# Brakeout_board_-_VEML7700.net
KiCad netlist of a schematic drawn in EAGLE
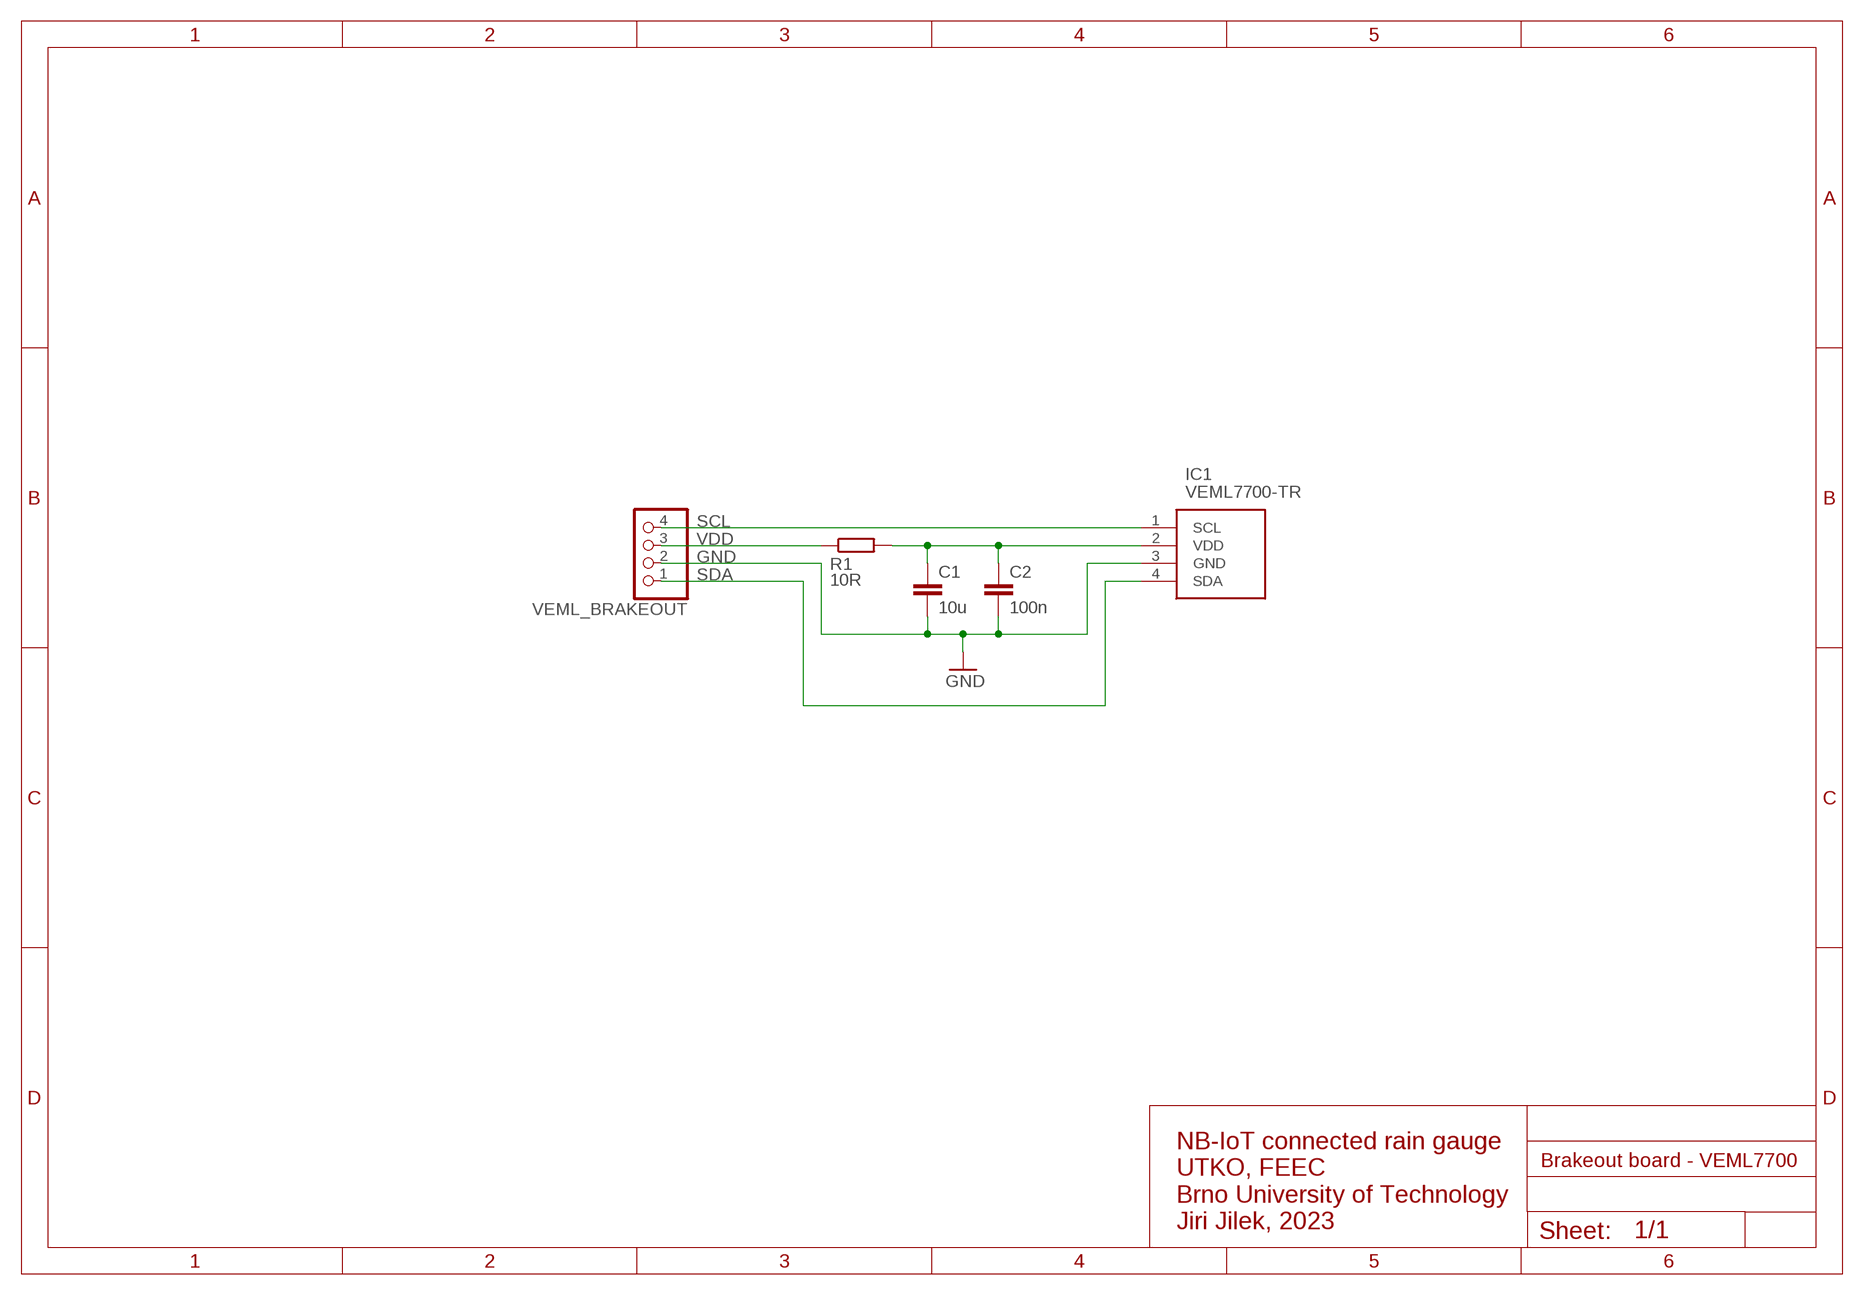
[diagram p0: schematic, sheet 1]

(export (version "E")
  (design (tool "Eeschema 10.0.6"))
  (components
    (comp (ref "C1")
      (value "10u")
      (footprint "eagle-import:C0805")
      (libsource (lib "eagle-import") (part "C-EUC0805"))
    )
    (comp (ref "C2")
      (value "100n")
      (footprint "eagle-import:C0805")
      (libsource (lib "eagle-import") (part "C-EUC0805"))
    )
    (comp (ref "IC1")
      (value "VEML7700-TR")
      (footprint "eagle-import:VEML7700")
      (fields (field (name "MOUSER_PART_NUMBER") "78-VEML7700-TR"))
      (libsource (lib "eagle-import") (part "VEML7700-TR"))
    )
    (comp (ref "R1")
      (value "10R")
      (footprint "eagle-import:R0805")
      (libsource (lib "eagle-import") (part "R-EU_R0805"))
    )
    (comp (ref "VEML_BRAKEOUT")
      (value "PINHD-1X4")
      (footprint "eagle-import:1X04")
      (libsource (lib "eagle-import") (part "PINHD-1X4"))
    )
  )
  (nets
    (net (code "1") (name "/SCL") (class "Default")
      (node (ref "IC1") (pin "1") (pinfunction "SCL_1") (pintype "bidirectional"))
      (node (ref "VEML_BRAKEOUT") (pin "4") (pinfunction "4_4") (pintype "passive"))
    )
    (net (code "2") (name "/SDA") (class "Default")
      (node (ref "IC1") (pin "4") (pinfunction "SDA_4") (pintype "bidirectional"))
      (node (ref "VEML_BRAKEOUT") (pin "1") (pinfunction "1_1") (pintype "passive"))
    )
    (net (code "3") (name "/VDD") (class "Default")
      (node (ref "R1") (pin "1") (pinfunction "1_1") (pintype "passive"))
      (node (ref "VEML_BRAKEOUT") (pin "3") (pinfunction "3_3") (pintype "passive"))
    )
    (net (code "4") (name "GND") (class "Default")
      (node (ref "C1") (pin "2") (pinfunction "2_2") (pintype "passive"))
      (node (ref "C2") (pin "2") (pinfunction "2_2") (pintype "passive"))
      (node (ref "IC1") (pin "3") (pinfunction "GND_3") (pintype "power_in"))
      (node (ref "VEML_BRAKEOUT") (pin "2") (pinfunction "2_2") (pintype "passive"))
    )
    (net (code "5") (name "Net-(IC1-VDD)") (class "Default")
      (node (ref "C1") (pin "1") (pinfunction "1_1") (pintype "passive"))
      (node (ref "C2") (pin "1") (pinfunction "1_1") (pintype "passive"))
      (node (ref "IC1") (pin "2") (pinfunction "VDD_2") (pintype "power_in"))
      (node (ref "R1") (pin "2") (pinfunction "2_2") (pintype "passive"))
    )
  )
)
